# Flow_sensor.net
KiCad netlist of a schematic drawn in Altium Designer
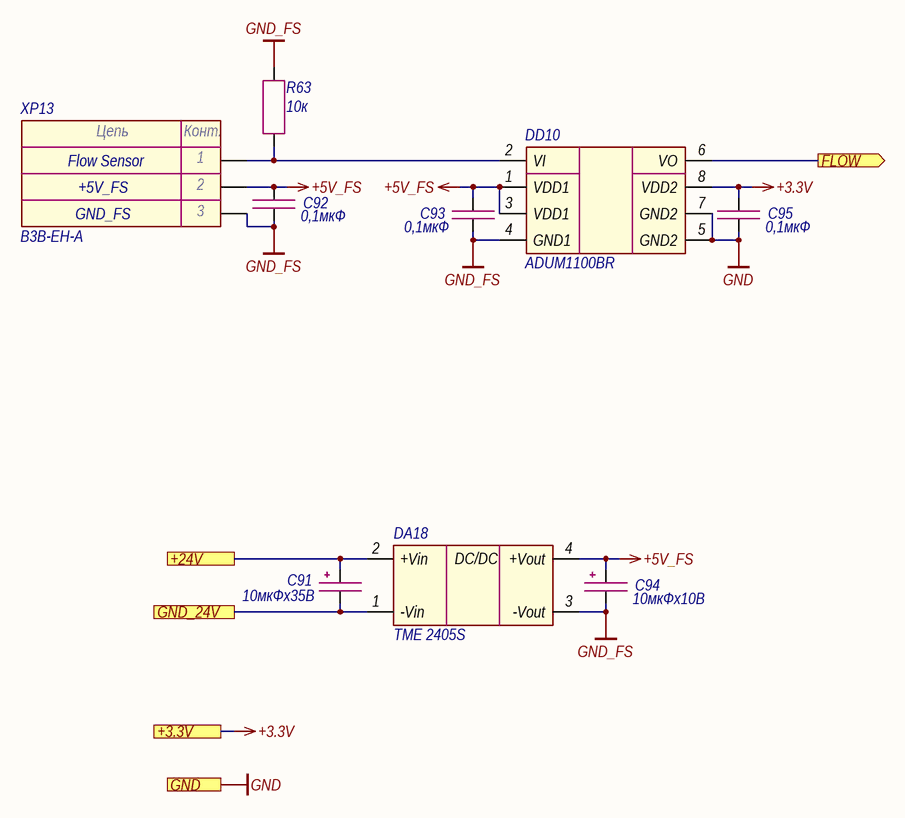
[diagram p0: Flow_sensor.SchDoc]

(export (version "E")
  (design (tool "Eeschema 10.0.6"))
  (components
    (comp (ref "C91")
      (value "10мкФх35B")
      (footprint "Pcb_library:CAP_C")
      (libsource (lib "Schem_library") (part "Capacitor_Polar"))
    )
    (comp (ref "C92")
      (value "0,1мкФ")
      (footprint "Pcb_library:CAP_0603")
      (fields (field (name "MANUFACTURER") "Murata"))
      (libsource (lib "Schem_library") (part "Capacitor"))
    )
    (comp (ref "C93")
      (value "0,1мкФ")
      (footprint "Pcb_library:CAP_0603")
      (fields (field (name "MANUFACTURER") "Murata"))
      (libsource (lib "Schem_library") (part "Capacitor"))
    )
    (comp (ref "C94")
      (value "10мкФх10B")
      (footprint "Pcb_library:CAP_A")
      (libsource (lib "Schem_library") (part "Capacitor_Polar"))
    )
    (comp (ref "C95")
      (value "0,1мкФ")
      (footprint "Pcb_library:CAP_0603")
      (fields (field (name "MANUFACTURER") "Murata"))
      (libsource (lib "Schem_library") (part "Capacitor"))
    )
    (comp (ref "DA18")
      (value "TME 2405S")
      (footprint "Pcb_library:TME (SIP-4)")
      (fields (field (name "MANUFACTURER") "Traco Power"))
      (libsource (lib "Schem_library") (part "TME"))
    )
    (comp (ref "DD10")
      (value "ADUM1100BR")
      (footprint "Pcb_library:SOIC-8")
      (fields (field (name "MANUFACTURER") "Analog Devices"))
      (libsource (lib "Schem_library") (part "ADUM1100"))
    )
    (comp (ref "R63")
      (value "10к")
      (footprint "Pcb_library:RES_0603")
      (fields (field (name "MANUFACTURER") "Yageo"))
      (libsource (lib "Schem_library") (part "Resistor"))
    )
    (comp (ref "XP13")
      (value "B3B-EH-A")
      (footprint "B3B-EH-A")
      (fields (field (name "MANUFACTURER") "JST"))
      (libsource (lib "Schem_library") (part "Connector-3"))
    )
  )
  (nets
    (net (code "1") (name "+3.3V") (class "Default")
      (node (ref "C95") (pin "1") (pinfunction "1_1") (pintype "passive"))
      (node (ref "DD10") (pin "8") (pinfunction "VDD2_8") (pintype "passive"))
    )
    (net (code "2") (name "+5V_FS") (class "Default")
      (node (ref "C92") (pin "1") (pinfunction "1_1") (pintype "passive"))
      (node (ref "C93") (pin "1") (pinfunction "1_1") (pintype "passive"))
      (node (ref "C94") (pin "1") (pinfunction "1_1") (pintype "passive"))
      (node (ref "DA18") (pin "4") (pinfunction "+Vout_4") (pintype "passive"))
      (node (ref "DD10") (pin "1") (pinfunction "VDD1_1") (pintype "passive"))
      (node (ref "DD10") (pin "3") (pinfunction "VDD1_3") (pintype "passive"))
      (node (ref "XP13") (pin "2") (pintype "passive"))
    )
    (net (code "3") (name "/+24V") (class "Default")
      (node (ref "C91") (pin "1") (pinfunction "1_1") (pintype "passive"))
      (node (ref "DA18") (pin "2") (pinfunction "+Vin_2") (pintype "passive"))
    )
    (net (code "4") (name "/FLOW") (class "Default")
      (node (ref "DD10") (pin "6") (pinfunction "VO_6") (pintype "passive"))
    )
    (net (code "5") (name "/GND_24V") (class "Default")
      (node (ref "C91") (pin "2") (pinfunction "2_2") (pintype "passive"))
      (node (ref "DA18") (pin "1") (pinfunction "-Vin_1") (pintype "passive"))
    )
    (net (code "6") (name "GND") (class "Default")
      (node (ref "C95") (pin "2") (pinfunction "2_2") (pintype "passive"))
      (node (ref "DD10") (pin "5") (pinfunction "GND2_5") (pintype "passive"))
      (node (ref "DD10") (pin "7") (pinfunction "GND2_7") (pintype "passive"))
    )
    (net (code "7") (name "GND_FS") (class "Default")
      (node (ref "C92") (pin "2") (pinfunction "2_2") (pintype "passive"))
      (node (ref "C93") (pin "2") (pinfunction "2_2") (pintype "passive"))
      (node (ref "C94") (pin "2") (pinfunction "2_2") (pintype "passive"))
      (node (ref "DA18") (pin "3") (pinfunction "-Vout_3") (pintype "passive"))
      (node (ref "DD10") (pin "4") (pinfunction "GND1_4") (pintype "passive"))
      (node (ref "R63") (pin "2") (pinfunction "2_2") (pintype "passive"))
      (node (ref "XP13") (pin "3") (pintype "passive"))
    )
    (net (code "8") (name "Net-(DD10-VI)") (class "Default")
      (node (ref "DD10") (pin "2") (pinfunction "VI_2") (pintype "passive"))
      (node (ref "R63") (pin "1") (pinfunction "1_1") (pintype "passive"))
      (node (ref "XP13") (pin "1") (pintype "passive"))
    )
  )
)
